# tick-mk-4_6_3.net
KiCad netlist of a schematic drawn in EAGLE
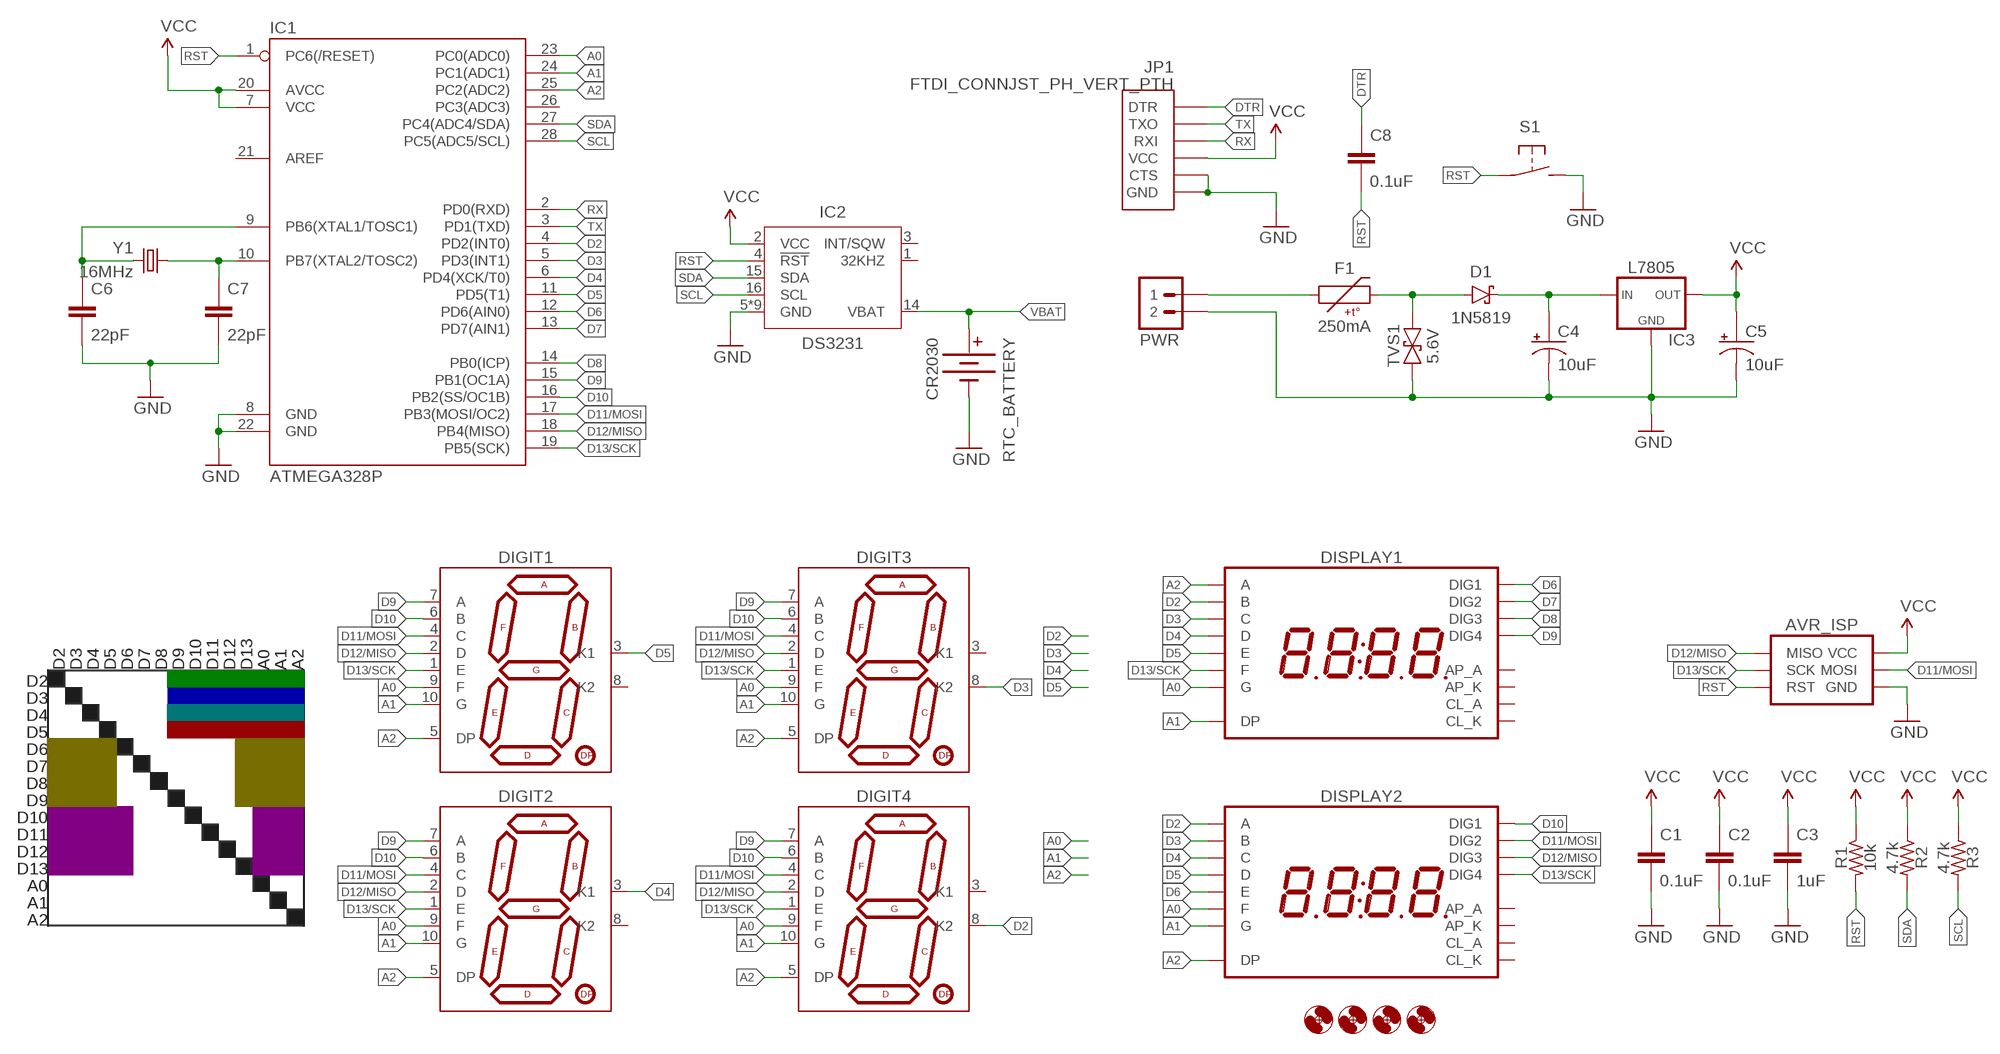
[diagram p0: schematic, sheet 1]

(export (version "E")
  (design (tool "Eeschema 10.0.6"))
  (components
    (comp (ref "AVR_ISP")
      (value "AVR_SPI_PRG_6PTH")
      (footprint "eagle-import:2X3")
      (libsource (lib "eagle-import") (part "AVR_SPI_PRG_6PTH"))
    )
    (comp (ref "C1")
      (value "0.1uF")
      (footprint "eagle-import:C025-024X044")
      (libsource (lib "eagle-import") (part "CAPACITOR-CERAMIC025-024X044"))
    )
    (comp (ref "C2")
      (value "0.1uF")
      (footprint "eagle-import:C025-024X044")
      (libsource (lib "eagle-import") (part "CAPACITOR-CERAMIC025-024X044"))
    )
    (comp (ref "C3")
      (value "1uF")
      (footprint "eagle-import:C025-024X044")
      (libsource (lib "eagle-import") (part "CAPACITOR-CERAMIC025-024X044"))
    )
    (comp (ref "C4")
      (value "10uF")
      (footprint "eagle-import:E2-5")
      (libsource (lib "eagle-import") (part "CAPACITOR-POLARIZEDE2-5"))
    )
    (comp (ref "C5")
      (value "10uF")
      (footprint "eagle-import:E2-5")
      (libsource (lib "eagle-import") (part "CAPACITOR-POLARIZEDE2-5"))
    )
    (comp (ref "C6")
      (value "22pF")
      (footprint "eagle-import:C025-024X044")
      (libsource (lib "eagle-import") (part "CAPACITOR-CERAMIC025-024X044"))
    )
    (comp (ref "C7")
      (value "22pF")
      (footprint "eagle-import:C025-024X044")
      (libsource (lib "eagle-import") (part "CAPACITOR-CERAMIC025-024X044"))
    )
    (comp (ref "C8")
      (value "0.1uF")
      (footprint "eagle-import:C025-024X044")
      (libsource (lib "eagle-import") (part "CAPACITOR-CERAMIC025-024X044"))
    )
    (comp (ref "D1")
      (value "1N5819")
      (footprint "eagle-import:DIODE-10.16MM")
      (libsource (lib "eagle-import") (part "DIODE-SCHOTTKYPTH-10.16MM"))
    )
    (comp (ref "DIGIT1")
      (value "7SEG_1DIGPTH-25.4MM-BARE")
      (footprint "eagle-import:7SEG_1DIG_25.4MM_NOSILK")
      (libsource (lib "eagle-import") (part "7SEG_1DIGPTH-25.4MM-BARE"))
    )
    (comp (ref "DIGIT2")
      (value "7SEG_1DIGPTH-25.4MM-BARE")
      (footprint "eagle-import:7SEG_1DIG_25.4MM_NOSILK")
      (libsource (lib "eagle-import") (part "7SEG_1DIGPTH-25.4MM-BARE"))
    )
    (comp (ref "DIGIT3")
      (value "7SEG_1DIGPTH-25.4MM-BARE")
      (footprint "eagle-import:7SEG_1DIG_25.4MM_NOSILK")
      (libsource (lib "eagle-import") (part "7SEG_1DIGPTH-25.4MM-BARE"))
    )
    (comp (ref "DIGIT4")
      (value "7SEG_1DIGPTH-25.4MM-BARE")
      (footprint "eagle-import:7SEG_1DIG_25.4MM_NOSILK")
      (libsource (lib "eagle-import") (part "7SEG_1DIGPTH-25.4MM-BARE"))
    )
    (comp (ref "DISPLAY1")
      (value "7SEG_4DIGIT_COLON_APOS")
      (footprint "eagle-import:7SEG_4DIG_10MM")
      (libsource (lib "eagle-import") (part "7SEG_4DIGIT_COLON_APOS"))
    )
    (comp (ref "DISPLAY2")
      (value "7SEG_4DIGIT_COLON_APOS")
      (footprint "eagle-import:7SEG_4DIG_10MM")
      (libsource (lib "eagle-import") (part "7SEG_4DIGIT_COLON_APOS"))
    )
    (comp (ref "F1")
      (value "250mA")
      (footprint "eagle-import:PTC-PTH-5.08MM")
      (libsource (lib "eagle-import") (part "PTCPTH-5.08MM"))
    )
    (comp (ref "H1")
      (value "HOLE#2")
      (footprint "eagle-import:HOLE-#2")
      (libsource (lib "eagle-import") (part "HOLE#2"))
    )
    (comp (ref "H2")
      (value "HOLE#2")
      (footprint "eagle-import:HOLE-#2")
      (libsource (lib "eagle-import") (part "HOLE#2"))
    )
    (comp (ref "H3")
      (value "HOLE#2")
      (footprint "eagle-import:HOLE-#2")
      (libsource (lib "eagle-import") (part "HOLE#2"))
    )
    (comp (ref "H4")
      (value "HOLE#2")
      (footprint "eagle-import:HOLE-#2")
      (libsource (lib "eagle-import") (part "HOLE#2"))
    )
    (comp (ref "IC1")
      (value "ATMEGA328P")
      (footprint "eagle-import:DIL28-3")
      (libsource (lib "eagle-import") (part "ATMEGA328P_PDIP"))
    )
    (comp (ref "IC2")
      (value "DS3231")
      (footprint "eagle-import:SO16W")
      (libsource (lib "eagle-import") (part "DS3231"))
    )
    (comp (ref "IC3")
      (value "L7805")
      (footprint "eagle-import:TO220-IGO-THERMPAD")
      (libsource (lib "eagle-import") (part "V_REG_78XXTO-220-THERMPAD"))
    )
    (comp (ref "JP1")
      (value "FTDI_CONNJST_PH_VERT_PTH")
      (footprint "eagle-import:FTDI_CONN_JST_PH_VERT_PTH")
      (libsource (lib "eagle-import") (part "FTDI_CONNJST_PH_VERT_PTH"))
    )
    (comp (ref "PWR")
      (value "M02JST-PTH-VERT")
      (footprint "eagle-import:JST-2-PH-VERT-PTH")
      (libsource (lib "eagle-import") (part "M02JST-PTH-VERT"))
    )
    (comp (ref "R1")
      (value "10k")
      (footprint "eagle-import:RESISTOR-AXIAL-PTH-7.62MM")
      (libsource (lib "eagle-import") (part "RESISTORPTH-AXIAL-7.62MM"))
    )
    (comp (ref "R2")
      (value "4.7k")
      (footprint "eagle-import:RESISTOR-AXIAL-PTH-6.35MM")
      (libsource (lib "eagle-import") (part "RESISTORPTH-AXIAL-6.35MM"))
    )
    (comp (ref "R3")
      (value "4.7k")
      (footprint "eagle-import:RESISTOR-AXIAL-PTH-6.35MM")
      (libsource (lib "eagle-import") (part "RESISTORPTH-AXIAL-6.35MM"))
    )
    (comp (ref "RTC_BATTERY")
      (value "CR2030")
      (footprint "eagle-import:BATTCON_20MM_MINE")
      (libsource (lib "eagle-import") (part "BATTERY20MMSMD-MINE"))
    )
    (comp (ref "S1")
      (value "SPST-NO-TACT6MM-SMD")
      (footprint "eagle-import:DTSM-6")
      (libsource (lib "eagle-import") (part "SPST-NO-TACT6MM-SMD"))
    )
    (comp (ref "TVS1")
      (value "5.6V")
      (footprint "eagle-import:DO-41-TVS-BI-10.16MM")
      (libsource (lib "eagle-import") (part "TVSDO-41-10.16MM"))
    )
    (comp (ref "Y1")
      (value "16MHz")
      (footprint "eagle-import:HC49U-V")
      (libsource (lib "eagle-import") (part "CRYSTALHC49UV"))
    )
  )
  (nets
    (net (code "1") (name "A0") (class "Default")
      (node (ref "DIGIT1") (pin "9") (pinfunction "F_9") (pintype "bidirectional"))
      (node (ref "DIGIT2") (pin "9") (pinfunction "F_9") (pintype "bidirectional"))
      (node (ref "DIGIT3") (pin "9") (pinfunction "F_9") (pintype "bidirectional"))
      (node (ref "DIGIT4") (pin "9") (pinfunction "F_9") (pintype "bidirectional"))
      (node (ref "DISPLAY1") (pin "15") (pinfunction "G_15") (pintype "passive"))
      (node (ref "DISPLAY2") (pin "11") (pinfunction "F_11") (pintype "passive"))
      (node (ref "IC1") (pin "23") (pinfunction "PC0(ADC0)_23") (pintype "bidirectional"))
    )
    (net (code "2") (name "A1") (class "Default")
      (node (ref "DIGIT1") (pin "10") (pinfunction "G_10") (pintype "bidirectional"))
      (node (ref "DIGIT2") (pin "10") (pinfunction "G_10") (pintype "bidirectional"))
      (node (ref "DIGIT3") (pin "10") (pinfunction "G_10") (pintype "bidirectional"))
      (node (ref "DIGIT4") (pin "10") (pinfunction "G_10") (pintype "bidirectional"))
      (node (ref "DISPLAY1") (pin "7") (pinfunction "DP_7") (pintype "passive"))
      (node (ref "DISPLAY2") (pin "15") (pinfunction "G_15") (pintype "passive"))
      (node (ref "IC1") (pin "24") (pinfunction "PC1(ADC1)_24") (pintype "bidirectional"))
    )
    (net (code "3") (name "A2") (class "Default")
      (node (ref "DIGIT1") (pin "5") (pinfunction "DP_5") (pintype "bidirectional"))
      (node (ref "DIGIT2") (pin "5") (pinfunction "DP_5") (pintype "bidirectional"))
      (node (ref "DIGIT3") (pin "5") (pinfunction "DP_5") (pintype "bidirectional"))
      (node (ref "DIGIT4") (pin "5") (pinfunction "DP_5") (pintype "bidirectional"))
      (node (ref "DISPLAY1") (pin "14") (pinfunction "A_14") (pintype "passive"))
      (node (ref "DISPLAY2") (pin "7") (pinfunction "DP_7") (pintype "passive"))
      (node (ref "IC1") (pin "25") (pinfunction "PC2(ADC2)_25") (pintype "bidirectional"))
    )
    (net (code "4") (name "D2") (class "Default")
      (node (ref "DIGIT4") (pin "8") (pinfunction "K2_8") (pintype "bidirectional"))
      (node (ref "DISPLAY1") (pin "16") (pinfunction "B_16") (pintype "passive"))
      (node (ref "DISPLAY2") (pin "14") (pinfunction "A_14") (pintype "passive"))
      (node (ref "IC1") (pin "4") (pinfunction "PD2(INT0)_4") (pintype "bidirectional"))
    )
    (net (code "5") (name "D3") (class "Default")
      (node (ref "DIGIT3") (pin "8") (pinfunction "K2_8") (pintype "bidirectional"))
      (node (ref "DISPLAY1") (pin "13") (pinfunction "C_13") (pintype "passive"))
      (node (ref "DISPLAY2") (pin "16") (pinfunction "B_16") (pintype "passive"))
      (node (ref "IC1") (pin "5") (pinfunction "PD3(INT1)_5") (pintype "bidirectional"))
    )
    (net (code "6") (name "D4") (class "Default")
      (node (ref "DIGIT2") (pin "3") (pinfunction "K1_3") (pintype "bidirectional"))
      (node (ref "DISPLAY1") (pin "3") (pinfunction "D_3") (pintype "passive"))
      (node (ref "DISPLAY2") (pin "13") (pinfunction "C_13") (pintype "passive"))
      (node (ref "IC1") (pin "6") (pinfunction "PD4(XCK/T0)_6") (pintype "bidirectional"))
    )
    (net (code "7") (name "D5") (class "Default")
      (node (ref "DIGIT1") (pin "3") (pinfunction "K1_3") (pintype "bidirectional"))
      (node (ref "DISPLAY1") (pin "5") (pinfunction "E_5") (pintype "passive"))
      (node (ref "DISPLAY2") (pin "3") (pinfunction "D_3") (pintype "passive"))
      (node (ref "IC1") (pin "11") (pinfunction "PD5(T1)_11") (pintype "bidirectional"))
    )
    (net (code "8") (name "D6") (class "Default")
      (node (ref "DISPLAY1") (pin "1") (pinfunction "DIG1_1") (pintype "passive"))
      (node (ref "DISPLAY2") (pin "5") (pinfunction "E_5") (pintype "passive"))
      (node (ref "IC1") (pin "12") (pinfunction "PD6(AIN0)_12") (pintype "bidirectional"))
    )
    (net (code "9") (name "D7") (class "Default")
      (node (ref "DISPLAY1") (pin "2") (pinfunction "DIG2_2") (pintype "passive"))
      (node (ref "IC1") (pin "13") (pinfunction "PD7(AIN1)_13") (pintype "bidirectional"))
    )
    (net (code "10") (name "D8") (class "Default")
      (node (ref "DISPLAY1") (pin "6") (pinfunction "DIG3_6") (pintype "passive"))
      (node (ref "IC1") (pin "14") (pinfunction "PB0(ICP)_14") (pintype "bidirectional"))
    )
    (net (code "11") (name "D9") (class "Default")
      (node (ref "DIGIT1") (pin "7") (pinfunction "A_7") (pintype "bidirectional"))
      (node (ref "DIGIT2") (pin "7") (pinfunction "A_7") (pintype "bidirectional"))
      (node (ref "DIGIT3") (pin "7") (pinfunction "A_7") (pintype "bidirectional"))
      (node (ref "DIGIT4") (pin "7") (pinfunction "A_7") (pintype "bidirectional"))
      (node (ref "DISPLAY1") (pin "8") (pinfunction "DIG4_8") (pintype "passive"))
      (node (ref "IC1") (pin "15") (pinfunction "PB1(OC1A)_15") (pintype "bidirectional"))
    )
    (net (code "12") (name "D10") (class "Default")
      (node (ref "DIGIT1") (pin "6") (pinfunction "B_6") (pintype "bidirectional"))
      (node (ref "DIGIT2") (pin "6") (pinfunction "B_6") (pintype "bidirectional"))
      (node (ref "DIGIT3") (pin "6") (pinfunction "B_6") (pintype "bidirectional"))
      (node (ref "DIGIT4") (pin "6") (pinfunction "B_6") (pintype "bidirectional"))
      (node (ref "DISPLAY2") (pin "1") (pinfunction "DIG1_1") (pintype "passive"))
      (node (ref "IC1") (pin "16") (pinfunction "PB2(SS/OC1B)_16") (pintype "bidirectional"))
    )
    (net (code "13") (name "D11{slash}MOSI") (class "Default")
      (node (ref "AVR_ISP") (pin "4") (pinfunction "MOSI_4") (pintype "passive"))
      (node (ref "DIGIT1") (pin "4") (pinfunction "C_4") (pintype "bidirectional"))
      (node (ref "DIGIT2") (pin "4") (pinfunction "C_4") (pintype "bidirectional"))
      (node (ref "DIGIT3") (pin "4") (pinfunction "C_4") (pintype "bidirectional"))
      (node (ref "DIGIT4") (pin "4") (pinfunction "C_4") (pintype "bidirectional"))
      (node (ref "DISPLAY2") (pin "2") (pinfunction "DIG2_2") (pintype "passive"))
      (node (ref "IC1") (pin "17") (pinfunction "PB3(MOSI/OC2)_17") (pintype "bidirectional"))
    )
    (net (code "14") (name "D12{slash}MISO") (class "Default")
      (node (ref "AVR_ISP") (pin "1") (pinfunction "MISO_1") (pintype "passive"))
      (node (ref "DIGIT1") (pin "2") (pinfunction "D_2") (pintype "bidirectional"))
      (node (ref "DIGIT2") (pin "2") (pinfunction "D_2") (pintype "bidirectional"))
      (node (ref "DIGIT3") (pin "2") (pinfunction "D_2") (pintype "bidirectional"))
      (node (ref "DIGIT4") (pin "2") (pinfunction "D_2") (pintype "bidirectional"))
      (node (ref "DISPLAY2") (pin "6") (pinfunction "DIG3_6") (pintype "passive"))
      (node (ref "IC1") (pin "18") (pinfunction "PB4(MISO)_18") (pintype "bidirectional"))
    )
    (net (code "15") (name "D13{slash}SCK") (class "Default")
      (node (ref "AVR_ISP") (pin "3") (pinfunction "SCK_3") (pintype "passive"))
      (node (ref "DIGIT1") (pin "1") (pinfunction "E_1") (pintype "bidirectional"))
      (node (ref "DIGIT2") (pin "1") (pinfunction "E_1") (pintype "bidirectional"))
      (node (ref "DIGIT3") (pin "1") (pinfunction "E_1") (pintype "bidirectional"))
      (node (ref "DIGIT4") (pin "1") (pinfunction "E_1") (pintype "bidirectional"))
      (node (ref "DISPLAY1") (pin "11") (pinfunction "F_11") (pintype "passive"))
      (node (ref "DISPLAY2") (pin "8") (pinfunction "DIG4_8") (pintype "passive"))
      (node (ref "IC1") (pin "19") (pinfunction "PB5(SCK)_19") (pintype "bidirectional"))
    )
    (net (code "16") (name "DTR") (class "Default")
      (node (ref "C8") (pin "1") (pinfunction "1_1") (pintype "passive"))
      (node (ref "JP1") (pin "DTR") (pinfunction "DTR_DTR") (pintype "bidirectional"))
    )
    (net (code "17") (name "GND") (class "Default")
      (node (ref "AVR_ISP") (pin "6") (pinfunction "GND_6") (pintype "passive"))
      (node (ref "C1") (pin "2") (pinfunction "2_2") (pintype "passive"))
      (node (ref "C2") (pin "2") (pinfunction "2_2") (pintype "passive"))
      (node (ref "C3") (pin "2") (pinfunction "2_2") (pintype "passive"))
      (node (ref "C4") (pin "-") (pinfunction "-_-") (pintype "passive"))
      (node (ref "C5") (pin "-") (pinfunction "-_-") (pintype "passive"))
      (node (ref "C6") (pin "2") (pinfunction "2_2") (pintype "passive"))
      (node (ref "C7") (pin "2") (pinfunction "2_2") (pintype "passive"))
      (node (ref "IC1") (pin "22") (pinfunction "GND_22") (pintype "bidirectional"))
      (node (ref "IC1") (pin "8") (pinfunction "GND_8") (pintype "bidirectional"))
      (node (ref "IC2") (pin "10") (pinfunction "GND_10") (pintype "bidirectional"))
      (node (ref "IC2") (pin "11") (pinfunction "GND_11") (pintype "bidirectional"))
      (node (ref "IC2") (pin "12") (pinfunction "GND_12") (pintype "bidirectional"))
      (node (ref "IC2") (pin "13") (pinfunction "GND_13") (pintype "bidirectional"))
      (node (ref "IC2") (pin "5") (pinfunction "GND_5") (pintype "bidirectional"))
      (node (ref "IC2") (pin "6") (pinfunction "GND_6") (pintype "bidirectional"))
      (node (ref "IC2") (pin "7") (pinfunction "GND_7") (pintype "bidirectional"))
      (node (ref "IC2") (pin "8") (pinfunction "GND_8") (pintype "bidirectional"))
      (node (ref "IC2") (pin "9") (pinfunction "GND_9") (pintype "bidirectional"))
      (node (ref "IC3") (pin "4") (pinfunction "GND_4") (pintype "bidirectional"))
      (node (ref "IC3") (pin "GND") (pinfunction "GND_GND") (pintype "bidirectional"))
      (node (ref "JP1") (pin "CTS") (pinfunction "CTS_CTS") (pintype "bidirectional"))
      (node (ref "JP1") (pin "GND") (pinfunction "GND_GND") (pintype "bidirectional"))
      (node (ref "PWR") (pin "2") (pinfunction "2_2") (pintype "passive"))
      (node (ref "RTC_BATTERY") (pin "BOTTOM") (pinfunction "-_BOTTOM") (pintype "power_in"))
      (node (ref "S1") (pin "3") (pinfunction "2_3") (pintype "passive"))
      (node (ref "S1") (pin "4") (pinfunction "2_4") (pintype "passive"))
      (node (ref "TVS1") (pin "P$1") (pinfunction "1_P$1") (pintype "passive"))
    )
    (net (code "18") (name "Net-(C4-Pad+)") (class "Default")
      (node (ref "C4") (pin "+") (pinfunction "+_+") (pintype "passive"))
      (node (ref "D1") (pin "C") (pinfunction "C_C") (pintype "passive"))
      (node (ref "IC3") (pin "IN") (pinfunction "IN_IN") (pintype "bidirectional"))
    )
    (net (code "19") (name "Net-(F1-1)") (class "Default")
      (node (ref "F1") (pin "P$1") (pinfunction "1_P$1") (pintype "passive"))
      (node (ref "PWR") (pin "1") (pinfunction "1_1") (pintype "passive"))
    )
    (net (code "20") (name "Net-(F1-2)") (class "Default")
      (node (ref "D1") (pin "A") (pinfunction "A_A") (pintype "passive"))
      (node (ref "F1") (pin "P$2") (pinfunction "2_P$2") (pintype "passive"))
      (node (ref "TVS1") (pin "P$2") (pinfunction "2_P$2") (pintype "passive"))
    )
    (net (code "21") (name "Net-(IC1-PB6(XTAL1{slash}TOSC1))") (class "Default")
      (node (ref "C6") (pin "1") (pinfunction "1_1") (pintype "passive"))
      (node (ref "IC1") (pin "9") (pinfunction "PB6(XTAL1/TOSC1)_9") (pintype "bidirectional"))
      (node (ref "Y1") (pin "2") (pinfunction "2_2") (pintype "passive"))
    )
    (net (code "22") (name "Net-(IC1-PB7(XTAL2{slash}TOSC2))") (class "Default")
      (node (ref "C7") (pin "1") (pinfunction "1_1") (pintype "passive"))
      (node (ref "IC1") (pin "10") (pinfunction "PB7(XTAL2/TOSC2)_10") (pintype "bidirectional"))
      (node (ref "Y1") (pin "1") (pinfunction "1_1") (pintype "passive"))
    )
    (net (code "23") (name "RST") (class "Default")
      (node (ref "AVR_ISP") (pin "5") (pinfunction "RST_5") (pintype "passive"))
      (node (ref "C8") (pin "2") (pinfunction "2_2") (pintype "passive"))
      (node (ref "IC1") (pin "1") (pinfunction "PC6(/RESET)_1") (pintype "bidirectional"))
      (node (ref "IC2") (pin "4") (pinfunction "~{RST}_4") (pintype "bidirectional"))
      (node (ref "R1") (pin "P$2") (pinfunction "2_P$2") (pintype "passive"))
      (node (ref "S1") (pin "1") (pinfunction "1_1") (pintype "passive"))
      (node (ref "S1") (pin "2") (pinfunction "1_2") (pintype "passive"))
    )
    (net (code "24") (name "RX") (class "Default")
      (node (ref "IC1") (pin "2") (pinfunction "PD0(RXD)_2") (pintype "bidirectional"))
      (node (ref "JP1") (pin "RXI") (pinfunction "RXI_RXI") (pintype "bidirectional"))
    )
    (net (code "25") (name "SCL") (class "Default")
      (node (ref "IC1") (pin "28") (pinfunction "PC5(ADC5/SCL)_28") (pintype "bidirectional"))
      (node (ref "IC2") (pin "16") (pinfunction "SCL_16") (pintype "bidirectional"))
      (node (ref "R3") (pin "P$2") (pinfunction "2_P$2") (pintype "passive"))
    )
    (net (code "26") (name "SDA") (class "Default")
      (node (ref "IC1") (pin "27") (pinfunction "PC4(ADC4/SDA)_27") (pintype "bidirectional"))
      (node (ref "IC2") (pin "15") (pinfunction "SDA_15") (pintype "bidirectional"))
      (node (ref "R2") (pin "P$2") (pinfunction "2_P$2") (pintype "passive"))
    )
    (net (code "27") (name "TX") (class "Default")
      (node (ref "IC1") (pin "3") (pinfunction "PD1(TXD)_3") (pintype "bidirectional"))
      (node (ref "JP1") (pin "TXO") (pinfunction "TXO_TXO") (pintype "bidirectional"))
    )
    (net (code "28") (name "VBAT") (class "Default")
      (node (ref "IC2") (pin "14") (pinfunction "VBAT_14") (pintype "bidirectional"))
      (node (ref "RTC_BATTERY") (pin "TOP@1") (pinfunction "+_TOP@1") (pintype "power_in"))
      (node (ref "RTC_BATTERY") (pin "TOP@2") (pinfunction "+_TOP@2") (pintype "power_in"))
    )
    (net (code "29") (name "VCC") (class "Default")
      (node (ref "AVR_ISP") (pin "2") (pinfunction "VCC_2") (pintype "passive"))
      (node (ref "C1") (pin "1") (pinfunction "1_1") (pintype "passive"))
      (node (ref "C2") (pin "1") (pinfunction "1_1") (pintype "passive"))
      (node (ref "C3") (pin "1") (pinfunction "1_1") (pintype "passive"))
      (node (ref "C5") (pin "+") (pinfunction "+_+") (pintype "passive"))
      (node (ref "IC1") (pin "20") (pinfunction "AVCC_20") (pintype "bidirectional"))
      (node (ref "IC1") (pin "7") (pinfunction "VCC_7") (pintype "bidirectional"))
      (node (ref "IC2") (pin "2") (pinfunction "VCC_2") (pintype "bidirectional"))
      (node (ref "IC3") (pin "OUT") (pinfunction "OUT_OUT") (pintype "bidirectional"))
      (node (ref "JP1") (pin "VCC") (pinfunction "VCC_VCC") (pintype "bidirectional"))
      (node (ref "R1") (pin "P$1") (pinfunction "1_P$1") (pintype "passive"))
      (node (ref "R2") (pin "P$1") (pinfunction "1_P$1") (pintype "passive"))
      (node (ref "R3") (pin "P$1") (pinfunction "1_P$1") (pintype "passive"))
    )
    (net (code "30") (name "unconnected-(DIGIT1-K2-Pad8)") (class "Default")
      (node (ref "DIGIT1") (pin "8") (pinfunction "K2_8") (pintype "bidirectional"))
    )
    (net (code "31") (name "unconnected-(DIGIT2-K2-Pad8)") (class "Default")
      (node (ref "DIGIT2") (pin "8") (pinfunction "K2_8") (pintype "bidirectional"))
    )
    (net (code "32") (name "unconnected-(DIGIT3-K1-Pad3)") (class "Default")
      (node (ref "DIGIT3") (pin "3") (pinfunction "K1_3") (pintype "bidirectional"))
    )
    (net (code "33") (name "unconnected-(DIGIT4-K1-Pad3)") (class "Default")
      (node (ref "DIGIT4") (pin "3") (pinfunction "K1_3") (pintype "bidirectional"))
    )
    (net (code "34") (name "unconnected-(DISPLAY1-AP_A-Pad10)") (class "Default")
      (node (ref "DISPLAY1") (pin "10") (pinfunction "AP_A_10") (pintype "bidirectional"))
    )
    (net (code "35") (name "unconnected-(DISPLAY1-AP_K-Pad9)") (class "Default")
      (node (ref "DISPLAY1") (pin "9") (pinfunction "AP_K_9") (pintype "bidirectional"))
    )
    (net (code "36") (name "unconnected-(DISPLAY1-CL_A-Pad4)") (class "Default")
      (node (ref "DISPLAY1") (pin "4") (pinfunction "CL_A_4") (pintype "passive"))
    )
    (net (code "37") (name "unconnected-(DISPLAY1-CL_K-Pad12)") (class "Default")
      (node (ref "DISPLAY1") (pin "12") (pinfunction "CL_K_12") (pintype "passive"))
    )
    (net (code "38") (name "unconnected-(DISPLAY2-AP_A-Pad10)") (class "Default")
      (node (ref "DISPLAY2") (pin "10") (pinfunction "AP_A_10") (pintype "bidirectional"))
    )
    (net (code "39") (name "unconnected-(DISPLAY2-AP_K-Pad9)") (class "Default")
      (node (ref "DISPLAY2") (pin "9") (pinfunction "AP_K_9") (pintype "bidirectional"))
    )
    (net (code "40") (name "unconnected-(DISPLAY2-CL_A-Pad4)") (class "Default")
      (node (ref "DISPLAY2") (pin "4") (pinfunction "CL_A_4") (pintype "passive"))
    )
    (net (code "41") (name "unconnected-(DISPLAY2-CL_K-Pad12)") (class "Default")
      (node (ref "DISPLAY2") (pin "12") (pinfunction "CL_K_12") (pintype "passive"))
    )
    (net (code "42") (name "unconnected-(IC1-AREF-Pad21)") (class "Default")
      (node (ref "IC1") (pin "21") (pinfunction "AREF_21") (pintype "bidirectional"))
    )
    (net (code "43") (name "unconnected-(IC1-PC3(ADC3)-Pad26)") (class "Default")
      (node (ref "IC1") (pin "26") (pinfunction "PC3(ADC3)_26") (pintype "bidirectional"))
    )
    (net (code "44") (name "unconnected-(IC2-32KHZ-Pad1)") (class "Default")
      (node (ref "IC2") (pin "1") (pinfunction "32KHZ_1") (pintype "bidirectional"))
    )
    (net (code "45") (name "unconnected-(IC2-INT{slash}SQW-Pad3)") (class "Default")
      (node (ref "IC2") (pin "3") (pinfunction "INT/SQW_3") (pintype "bidirectional"))
    )
  )
)
